# BBC_2024_REUSE.net
KiCad netlist of a schematic drawn in EasyEDA Pro
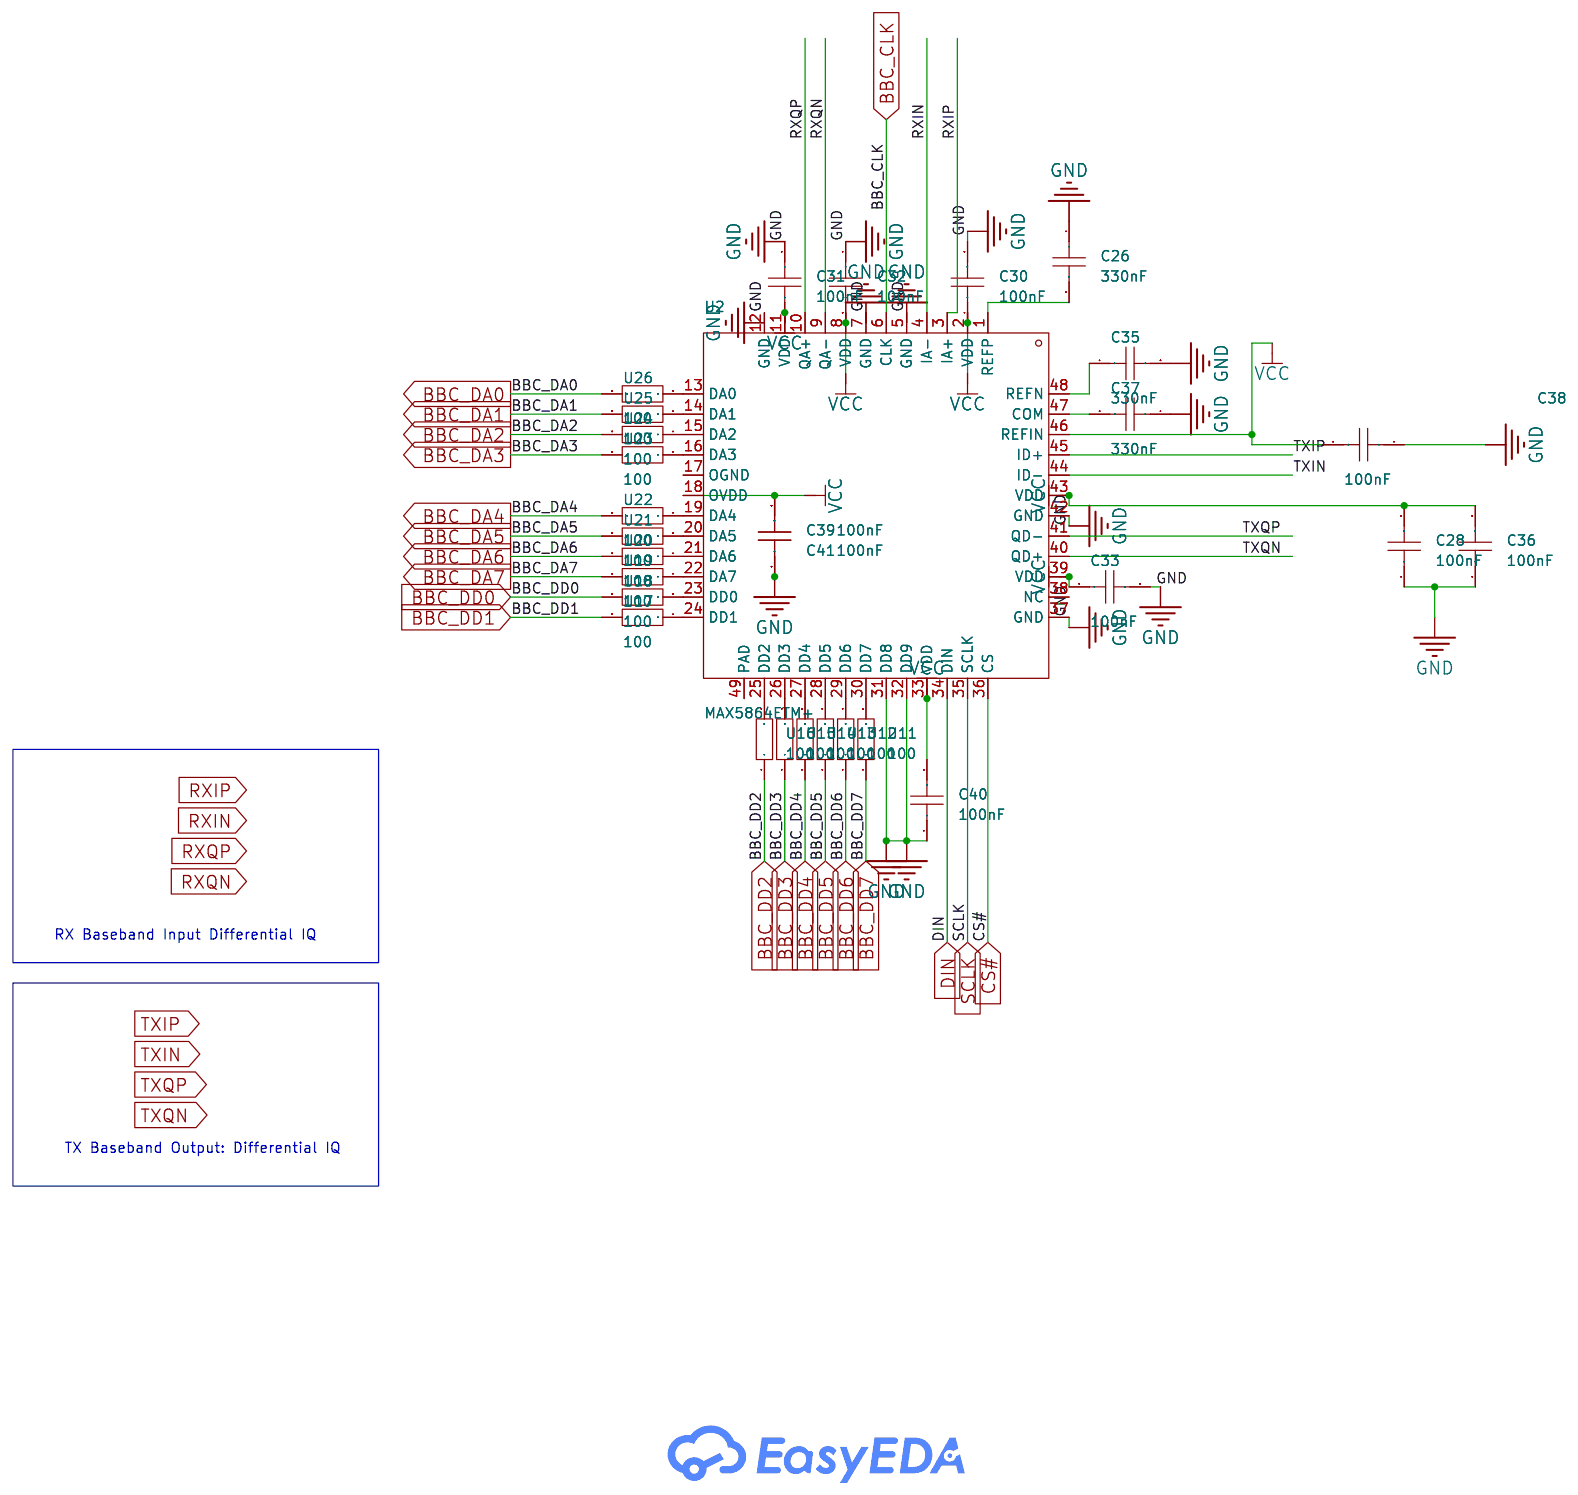
[diagram p0: schematic sheet]

(export (version "E")
  (design (tool "Eeschema 10.0.6"))
  (components
    (comp (ref "C26")
      (value "330nF")
      (footprint "easyedapro:C0805")
      (libsource (lib "easyedapro") (part "CAP"))
    )
    (comp (ref "C28")
      (value "100nF")
      (footprint "easyedapro:C0805")
      (libsource (lib "easyedapro") (part "CAP"))
    )
    (comp (ref "C30")
      (value "100nF")
      (footprint "easyedapro:C0805")
      (libsource (lib "easyedapro") (part "CAP"))
    )
    (comp (ref "C31")
      (value "100nF")
      (footprint "easyedapro:C0805")
      (libsource (lib "easyedapro") (part "CAP"))
    )
    (comp (ref "C32")
      (value "100nF")
      (footprint "easyedapro:C0805")
      (libsource (lib "easyedapro") (part "CAP"))
    )
    (comp (ref "C33")
      (value "100nF")
      (footprint "easyedapro:C0805")
      (libsource (lib "easyedapro") (part "CAP"))
    )
    (comp (ref "C35")
      (value "330nF")
      (footprint "easyedapro:C0805")
      (libsource (lib "easyedapro") (part "CAP"))
    )
    (comp (ref "C36")
      (value "100nF")
      (footprint "easyedapro:C0805")
      (libsource (lib "easyedapro") (part "CAP"))
    )
    (comp (ref "C37")
      (value "330nF")
      (footprint "easyedapro:C0805")
      (libsource (lib "easyedapro") (part "CAP"))
    )
    (comp (ref "C38")
      (value "100nF")
      (footprint "easyedapro:C0805")
      (libsource (lib "easyedapro") (part "CAP"))
    )
    (comp (ref "C39")
      (value "100nF")
      (footprint "easyedapro:C0805")
      (libsource (lib "easyedapro") (part "CAP"))
    )
    (comp (ref "C40")
      (value "100nF")
      (footprint "easyedapro:C0805")
      (libsource (lib "easyedapro") (part "CAP"))
    )
    (comp (ref "C41")
      (value "100nF")
      (footprint "easyedapro:C0805")
      (libsource (lib "easyedapro") (part "CAP"))
    )
    (comp (ref "U2")
      (value "MAX5864ETM+")
      (footprint "easyedapro:QFN-48_L7.0-W7.0-P0.50-BL-EP5.1")
      (description "Supply Voltage:2.7V~3.3V Supply Voltage:2.7V~3.3V")
      (fields (field (name "Manufacturer") "ADI(亚德诺)/MAXIM(美信)"))
      (libsource (lib "easyedapro") (part "MAX5864ETM+"))
    )
    (comp (ref "U11")
      (value "100")
      (footprint "easyedapro:R0805")
      (libsource (lib "easyedapro") (part "3R00"))
    )
    (comp (ref "U12")
      (value "100")
      (footprint "easyedapro:R0805")
      (libsource (lib "easyedapro") (part "3R00"))
    )
    (comp (ref "U13")
      (value "100")
      (footprint "easyedapro:R0805")
      (libsource (lib "easyedapro") (part "3R00"))
    )
    (comp (ref "U14")
      (value "100")
      (footprint "easyedapro:R0805")
      (libsource (lib "easyedapro") (part "3R00"))
    )
    (comp (ref "U15")
      (value "100")
      (footprint "easyedapro:R0805")
      (libsource (lib "easyedapro") (part "3R00"))
    )
    (comp (ref "U16")
      (value "100")
      (footprint "easyedapro:R0805")
      (libsource (lib "easyedapro") (part "3R00"))
    )
    (comp (ref "U17")
      (value "100")
      (footprint "easyedapro:R0805")
      (libsource (lib "easyedapro") (part "3R00"))
    )
    (comp (ref "U18")
      (value "100")
      (footprint "easyedapro:R0805")
      (libsource (lib "easyedapro") (part "3R00"))
    )
    (comp (ref "U19")
      (value "100")
      (footprint "easyedapro:R0805")
      (libsource (lib "easyedapro") (part "3R00"))
    )
    (comp (ref "U20")
      (value "100")
      (footprint "easyedapro:R0805")
      (libsource (lib "easyedapro") (part "3R00"))
    )
    (comp (ref "U21")
      (value "100")
      (footprint "easyedapro:R0805")
      (libsource (lib "easyedapro") (part "3R00"))
    )
    (comp (ref "U22")
      (value "100")
      (footprint "easyedapro:R0805")
      (libsource (lib "easyedapro") (part "3R00"))
    )
    (comp (ref "U23")
      (value "100")
      (footprint "easyedapro:R0805")
      (libsource (lib "easyedapro") (part "3R00"))
    )
    (comp (ref "U24")
      (value "100")
      (footprint "easyedapro:R0805")
      (libsource (lib "easyedapro") (part "3R00"))
    )
    (comp (ref "U25")
      (value "100")
      (footprint "easyedapro:R0805")
      (libsource (lib "easyedapro") (part "3R00"))
    )
    (comp (ref "U26")
      (value "100")
      (footprint "easyedapro:R0805")
      (libsource (lib "easyedapro") (part "3R00"))
    )
  )
  (nets
    (net (code "1") (name "BBC_CLK") (class "Default")
      (node (ref "U2") (pin "6") (pinfunction "CLK_6") (pintype "unspecified"))
    )
    (net (code "2") (name "BBC_DA0") (class "Default")
      (node (ref "U26") (pin "2") (pinfunction "2_2") (pintype "unspecified"))
    )
    (net (code "3") (name "BBC_DA1") (class "Default")
      (node (ref "U25") (pin "2") (pinfunction "2_2") (pintype "unspecified"))
    )
    (net (code "4") (name "BBC_DA2") (class "Default")
      (node (ref "U24") (pin "2") (pinfunction "2_2") (pintype "unspecified"))
    )
    (net (code "5") (name "BBC_DA3") (class "Default")
      (node (ref "U23") (pin "2") (pinfunction "2_2") (pintype "unspecified"))
    )
    (net (code "6") (name "BBC_DA4") (class "Default")
      (node (ref "U22") (pin "2") (pinfunction "2_2") (pintype "unspecified"))
    )
    (net (code "7") (name "BBC_DA5") (class "Default")
      (node (ref "U21") (pin "2") (pinfunction "2_2") (pintype "unspecified"))
    )
    (net (code "8") (name "BBC_DA6") (class "Default")
      (node (ref "U20") (pin "2") (pinfunction "2_2") (pintype "unspecified"))
    )
    (net (code "9") (name "BBC_DA7") (class "Default")
      (node (ref "U19") (pin "2") (pinfunction "2_2") (pintype "unspecified"))
    )
    (net (code "10") (name "BBC_DD0") (class "Default")
      (node (ref "U18") (pin "2") (pinfunction "2_2") (pintype "unspecified"))
    )
    (net (code "11") (name "BBC_DD1") (class "Default")
      (node (ref "U17") (pin "2") (pinfunction "2_2") (pintype "unspecified"))
    )
    (net (code "12") (name "BBC_DD2") (class "Default")
      (node (ref "U16") (pin "1") (pinfunction "1_1") (pintype "unspecified"))
    )
    (net (code "13") (name "BBC_DD3") (class "Default")
      (node (ref "U15") (pin "1") (pinfunction "1_1") (pintype "unspecified"))
    )
    (net (code "14") (name "BBC_DD4") (class "Default")
      (node (ref "U14") (pin "1") (pinfunction "1_1") (pintype "unspecified"))
    )
    (net (code "15") (name "BBC_DD5") (class "Default")
      (node (ref "U13") (pin "1") (pinfunction "1_1") (pintype "unspecified"))
    )
    (net (code "16") (name "BBC_DD6") (class "Default")
      (node (ref "U12") (pin "1") (pinfunction "1_1") (pintype "unspecified"))
    )
    (net (code "17") (name "BBC_DD7") (class "Default")
      (node (ref "U11") (pin "1") (pinfunction "1_1") (pintype "unspecified"))
    )
    (net (code "18") (name "CS#") (class "Default")
      (node (ref "U2") (pin "36") (pinfunction "CS_36") (pintype "unspecified"))
    )
    (net (code "19") (name "DIN") (class "Default")
      (node (ref "U2") (pin "34") (pinfunction "DIN_34") (pintype "unspecified"))
    )
    (net (code "20") (name "GND") (class "Default")
      (node (ref "C26") (pin "1") (pinfunction "1_1") (pintype "input"))
      (node (ref "C28") (pin "1") (pinfunction "1_1") (pintype "input"))
      (node (ref "C30") (pin "2") (pinfunction "2_2") (pintype "input"))
      (node (ref "C31") (pin "1") (pinfunction "1_1") (pintype "input"))
      (node (ref "C32") (pin "1") (pinfunction "1_1") (pintype "input"))
      (node (ref "C33") (pin "2") (pinfunction "2_2") (pintype "input"))
      (node (ref "C35") (pin "2") (pinfunction "2_2") (pintype "input"))
      (node (ref "C36") (pin "1") (pinfunction "1_1") (pintype "input"))
      (node (ref "C37") (pin "1") (pinfunction "1_1") (pintype "input"))
      (node (ref "C38") (pin "1") (pinfunction "1_1") (pintype "input"))
      (node (ref "C39") (pin "1") (pinfunction "1_1") (pintype "input"))
      (node (ref "C40") (pin "1") (pinfunction "1_1") (pintype "input"))
      (node (ref "C41") (pin "1") (pinfunction "1_1") (pintype "input"))
      (node (ref "U2") (pin "12") (pinfunction "GND_12") (pintype "unspecified"))
      (node (ref "U2") (pin "31") (pinfunction "DD8_31") (pintype "unspecified"))
      (node (ref "U2") (pin "32") (pinfunction "DD9_32") (pintype "unspecified"))
      (node (ref "U2") (pin "37") (pinfunction "GND_37") (pintype "unspecified"))
      (node (ref "U2") (pin "42") (pinfunction "GND_42") (pintype "unspecified"))
      (node (ref "U2") (pin "5") (pinfunction "GND_5") (pintype "unspecified"))
      (node (ref "U2") (pin "7") (pinfunction "GND_7") (pintype "unspecified"))
    )
    (net (code "21") (name "Net-(U2-COM)") (class "Default")
      (node (ref "C37") (pin "2") (pinfunction "2_2") (pintype "input"))
      (node (ref "U2") (pin "47") (pinfunction "COM_47") (pintype "unspecified"))
    )
    (net (code "22") (name "Net-(U2-DA0)") (class "Default")
      (node (ref "U2") (pin "13") (pinfunction "DA0_13") (pintype "unspecified"))
      (node (ref "U26") (pin "1") (pinfunction "1_1") (pintype "unspecified"))
    )
    (net (code "23") (name "Net-(U2-DA1)") (class "Default")
      (node (ref "U2") (pin "14") (pinfunction "DA1_14") (pintype "unspecified"))
      (node (ref "U25") (pin "1") (pinfunction "1_1") (pintype "unspecified"))
    )
    (net (code "24") (name "Net-(U2-DA2)") (class "Default")
      (node (ref "U2") (pin "15") (pinfunction "DA2_15") (pintype "unspecified"))
      (node (ref "U24") (pin "1") (pinfunction "1_1") (pintype "unspecified"))
    )
    (net (code "25") (name "Net-(U2-DA3)") (class "Default")
      (node (ref "U2") (pin "16") (pinfunction "DA3_16") (pintype "unspecified"))
      (node (ref "U23") (pin "1") (pinfunction "1_1") (pintype "unspecified"))
    )
    (net (code "26") (name "Net-(U2-DA4)") (class "Default")
      (node (ref "U2") (pin "19") (pinfunction "DA4_19") (pintype "unspecified"))
      (node (ref "U22") (pin "1") (pinfunction "1_1") (pintype "unspecified"))
    )
    (net (code "27") (name "Net-(U2-DA5)") (class "Default")
      (node (ref "U2") (pin "20") (pinfunction "DA5_20") (pintype "unspecified"))
      (node (ref "U21") (pin "1") (pinfunction "1_1") (pintype "unspecified"))
    )
    (net (code "28") (name "Net-(U2-DA6)") (class "Default")
      (node (ref "U2") (pin "21") (pinfunction "DA6_21") (pintype "unspecified"))
      (node (ref "U20") (pin "1") (pinfunction "1_1") (pintype "unspecified"))
    )
    (net (code "29") (name "Net-(U2-DA7)") (class "Default")
      (node (ref "U19") (pin "1") (pinfunction "1_1") (pintype "unspecified"))
      (node (ref "U2") (pin "22") (pinfunction "DA7_22") (pintype "unspecified"))
    )
    (net (code "30") (name "Net-(U2-DD0)") (class "Default")
      (node (ref "U18") (pin "1") (pinfunction "1_1") (pintype "unspecified"))
      (node (ref "U2") (pin "23") (pinfunction "DD0_23") (pintype "unspecified"))
    )
    (net (code "31") (name "Net-(U2-DD1)") (class "Default")
      (node (ref "U17") (pin "1") (pinfunction "1_1") (pintype "unspecified"))
      (node (ref "U2") (pin "24") (pinfunction "DD1_24") (pintype "unspecified"))
    )
    (net (code "32") (name "Net-(U2-DD2)") (class "Default")
      (node (ref "U16") (pin "2") (pinfunction "2_2") (pintype "unspecified"))
      (node (ref "U2") (pin "25") (pinfunction "DD2_25") (pintype "unspecified"))
    )
    (net (code "33") (name "Net-(U2-DD3)") (class "Default")
      (node (ref "U15") (pin "2") (pinfunction "2_2") (pintype "unspecified"))
      (node (ref "U2") (pin "26") (pinfunction "DD3_26") (pintype "unspecified"))
    )
    (net (code "34") (name "Net-(U2-DD4)") (class "Default")
      (node (ref "U14") (pin "2") (pinfunction "2_2") (pintype "unspecified"))
      (node (ref "U2") (pin "27") (pinfunction "DD4_27") (pintype "unspecified"))
    )
    (net (code "35") (name "Net-(U2-DD5)") (class "Default")
      (node (ref "U13") (pin "2") (pinfunction "2_2") (pintype "unspecified"))
      (node (ref "U2") (pin "28") (pinfunction "DD5_28") (pintype "unspecified"))
    )
    (net (code "36") (name "Net-(U2-DD6)") (class "Default")
      (node (ref "U12") (pin "2") (pinfunction "2_2") (pintype "unspecified"))
      (node (ref "U2") (pin "29") (pinfunction "DD6_29") (pintype "unspecified"))
    )
    (net (code "37") (name "Net-(U2-DD7)") (class "Default")
      (node (ref "U11") (pin "2") (pinfunction "2_2") (pintype "unspecified"))
      (node (ref "U2") (pin "30") (pinfunction "DD7_30") (pintype "unspecified"))
    )
    (net (code "38") (name "Net-(U2-REFN)") (class "Default")
      (node (ref "C35") (pin "1") (pinfunction "1_1") (pintype "input"))
      (node (ref "U2") (pin "48") (pinfunction "REFN_48") (pintype "unspecified"))
    )
    (net (code "39") (name "Net-(U2-REFP)") (class "Default")
      (node (ref "C26") (pin "2") (pinfunction "2_2") (pintype "input"))
      (node (ref "U2") (pin "1") (pinfunction "REFP_1") (pintype "unspecified"))
    )
    (net (code "40") (name "RXIN") (class "Default")
      (node (ref "U2") (pin "4") (pinfunction "IA-_4") (pintype "unspecified"))
    )
    (net (code "41") (name "RXIP") (class "Default")
      (node (ref "U2") (pin "3") (pinfunction "IA+_3") (pintype "unspecified"))
    )
    (net (code "42") (name "RXQN") (class "Default")
      (node (ref "U2") (pin "9") (pinfunction "QA-_9") (pintype "unspecified"))
    )
    (net (code "43") (name "RXQP") (class "Default")
      (node (ref "U2") (pin "10") (pinfunction "QA+_10") (pintype "unspecified"))
    )
    (net (code "44") (name "SCLK") (class "Default")
      (node (ref "U2") (pin "35") (pinfunction "SCLK_35") (pintype "unspecified"))
    )
    (net (code "45") (name "TXIN") (class "Default")
      (node (ref "U2") (pin "44") (pinfunction "ID-_44") (pintype "unspecified"))
    )
    (net (code "46") (name "TXIP") (class "Default")
      (node (ref "U2") (pin "45") (pinfunction "ID+_45") (pintype "unspecified"))
    )
    (net (code "47") (name "TXQN") (class "Default")
      (node (ref "U2") (pin "40") (pinfunction "QD+_40") (pintype "unspecified"))
    )
    (net (code "48") (name "TXQP") (class "Default")
      (node (ref "U2") (pin "41") (pinfunction "QD-_41") (pintype "unspecified"))
    )
    (net (code "49") (name "VCC") (class "Default")
      (node (ref "C28") (pin "2") (pinfunction "2_2") (pintype "input"))
      (node (ref "C30") (pin "1") (pinfunction "1_1") (pintype "input"))
      (node (ref "C31") (pin "2") (pinfunction "2_2") (pintype "input"))
      (node (ref "C32") (pin "2") (pinfunction "2_2") (pintype "input"))
      (node (ref "C33") (pin "1") (pinfunction "1_1") (pintype "input"))
      (node (ref "C36") (pin "2") (pinfunction "2_2") (pintype "input"))
      (node (ref "C38") (pin "2") (pinfunction "2_2") (pintype "input"))
      (node (ref "C39") (pin "2") (pinfunction "2_2") (pintype "input"))
      (node (ref "C40") (pin "2") (pinfunction "2_2") (pintype "input"))
      (node (ref "C41") (pin "2") (pinfunction "2_2") (pintype "input"))
      (node (ref "U2") (pin "11") (pinfunction "VDD_11") (pintype "unspecified"))
      (node (ref "U2") (pin "18") (pinfunction "OVDD_18") (pintype "unspecified"))
      (node (ref "U2") (pin "2") (pinfunction "VDD_2") (pintype "unspecified"))
      (node (ref "U2") (pin "33") (pinfunction "VDD_33") (pintype "unspecified"))
      (node (ref "U2") (pin "39") (pinfunction "VDD_39") (pintype "unspecified"))
      (node (ref "U2") (pin "43") (pinfunction "VDD_43") (pintype "unspecified"))
      (node (ref "U2") (pin "46") (pinfunction "REFIN_46") (pintype "unspecified"))
      (node (ref "U2") (pin "8") (pinfunction "VDD_8") (pintype "unspecified"))
    )
    (net (code "50") (name "unconnected-(U2-NC-Pad38)") (class "Default")
      (node (ref "U2") (pin "38") (pinfunction "NC_38") (pintype "unspecified"))
    )
    (net (code "51") (name "unconnected-(U2-OGND-Pad17)") (class "Default")
      (node (ref "U2") (pin "17") (pinfunction "OGND_17") (pintype "unspecified"))
    )
    (net (code "52") (name "unconnected-(U2-PAD-Pad49)") (class "Default")
      (node (ref "U2") (pin "49") (pinfunction "PAD_49") (pintype "unspecified"))
    )
  )
)
